# Focuser.net
KiCad netlist of a schematic drawn in EAGLE
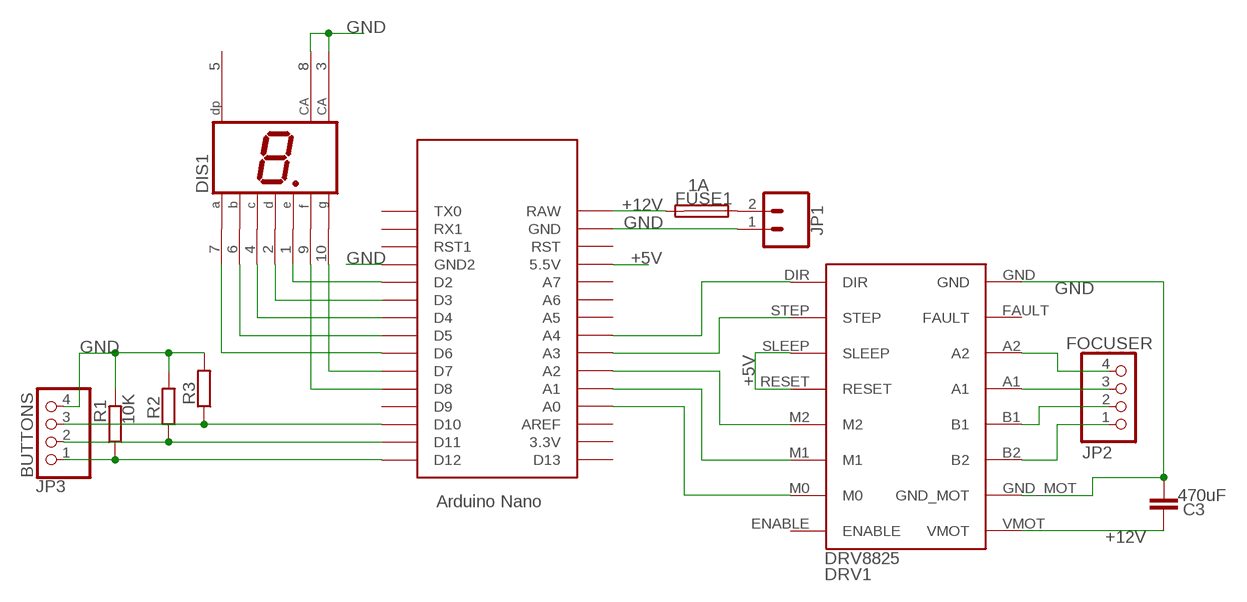
[diagram p0: schematic, sheet 1]

(export (version "E")
  (design (tool "Eeschema 10.0.6"))
  (components
    (comp (ref "C3")
      (value "470uF")
      (footprint "eagle-import:C5B2.5")
      (fields (field (name "SPICEPREFIX") "C"))
      (libsource (lib "eagle-import") (part "C5/2.5"))
    )
    (comp (ref "DIS1")
      (value "HD-H101")
      (footprint "eagle-import:HDSP-M")
      (fields (field (name "SPICEPREFIX") "X"))
      (libsource (lib "eagle-import") (part "HD-H101"))
    )
    (comp (ref "DRV1")
      (value "DRV8825")
      (footprint "eagle-import:DRV8825")
      (fields (field (name "SPICEPREFIX") "X"))
      (libsource (lib "eagle-import") (part "DRV8825"))
    )
    (comp (ref "FUSE1")
      (value "1A")
      (footprint "eagle-import:FUSE_HOLDER_5X20MM")
      (fields (field (name "SPICEPREFIX") "F"))
      (libsource (lib "eagle-import") (part "FUSEBLANK_5X20MM"))
    )
    (comp (ref "JP1")
      (value "CONN_025MM")
      (footprint "eagle-import:SCREWTERMINAL-5MM-2")
      (fields (field (name "SPICEPREFIX") "B"))
      (libsource (lib "eagle-import") (part "CONN_025MM"))
    )
    (comp (ref "JP2")
      (value "FOCUSER")
      (footprint "eagle-import:1X04")
      (fields (field (name "SPICEPREFIX") "E"))
      (libsource (lib "eagle-import") (part "PINHD-1X4"))
    )
    (comp (ref "JP3")
      (value "BUTTONS")
      (footprint "eagle-import:1X04")
      (fields (field (name "SPICEPREFIX") "E"))
      (libsource (lib "eagle-import") (part "PINHD-1X4"))
    )
    (comp (ref "R1")
      (value "10K")
      (footprint "eagle-import:0204V")
      (fields (field (name "SPICEPREFIX") "R"))
      (libsource (lib "eagle-import") (part "R-EU_0204/2V"))
    )
    (comp (ref "R2")
      (value "10K")
      (footprint "eagle-import:0204V")
      (fields (field (name "SPICEPREFIX") "R"))
      (libsource (lib "eagle-import") (part "R-EU_0204/2V"))
    )
    (comp (ref "R3")
      (value "10K")
      (footprint "eagle-import:0204V")
      (fields (field (name "SPICEPREFIX") "R"))
      (libsource (lib "eagle-import") (part "R-EU_0204/2V"))
    )
    (comp (ref "U$1")
      (value "NANO")
      (footprint "eagle-import:NANO")
      (fields (field (name "SPICEPREFIX") "X"))
      (libsource (lib "eagle-import") (part "NANO"))
    )
  )
  (nets
    (net (code "1") (name "/+5V") (class "Default")
      (node (ref "DRV1") (pin "RESET") (pinfunction "RESET_RESET") (pintype "bidirectional"))
      (node (ref "DRV1") (pin "SLEEP") (pinfunction "SLEEP_SLEEP") (pintype "bidirectional"))
      (node (ref "U$1") (pin "5V") (pinfunction "5.5V_5V") (pintype "bidirectional"))
    )
    (net (code "2") (name "/+12V") (class "Default")
      (node (ref "C3") (pin "2") (pinfunction "2_2") (pintype "passive"))
      (node (ref "DRV1") (pin "VMOT") (pinfunction "VMOT_VMOT") (pintype "bidirectional"))
      (node (ref "FUSE1") (pin "2") (pinfunction "2_2") (pintype "passive"))
      (node (ref "U$1") (pin "RAW") (pinfunction "RAW_RAW") (pintype "bidirectional"))
    )
    (net (code "3") (name "/GND") (class "Default")
      (node (ref "C3") (pin "1") (pinfunction "1_1") (pintype "passive"))
      (node (ref "DIS1") (pin "3") (pinfunction "CA_3") (pintype "passive"))
      (node (ref "DIS1") (pin "8") (pinfunction "CA_8") (pintype "passive"))
      (node (ref "DRV1") (pin "GND") (pinfunction "GND_GND") (pintype "bidirectional"))
      (node (ref "DRV1") (pin "GND_MOT") (pinfunction "GND_MOT_GND_MOT") (pintype "bidirectional"))
      (node (ref "JP1") (pin "1") (pinfunction "1_1") (pintype "passive"))
      (node (ref "JP3") (pin "4") (pinfunction "4_4") (pintype "passive"))
      (node (ref "R1") (pin "2") (pinfunction "2_2") (pintype "passive"))
      (node (ref "R2") (pin "2") (pinfunction "2_2") (pintype "passive"))
      (node (ref "R3") (pin "2") (pinfunction "2_2") (pintype "passive"))
      (node (ref "U$1") (pin "GND") (pinfunction "GND_GND") (pintype "bidirectional"))
      (node (ref "U$1") (pin "GND1") (pinfunction "GND2_GND1") (pintype "bidirectional"))
    )
    (net (code "4") (name "Net-(DIS1-A)") (class "Default")
      (node (ref "DIS1") (pin "7") (pinfunction "A_7") (pintype "passive"))
      (node (ref "U$1") (pin "D6") (pinfunction "D6_D6") (pintype "bidirectional"))
    )
    (net (code "5") (name "Net-(DIS1-B)") (class "Default")
      (node (ref "DIS1") (pin "6") (pinfunction "B_6") (pintype "passive"))
      (node (ref "U$1") (pin "D5") (pinfunction "D5_D5") (pintype "bidirectional"))
    )
    (net (code "6") (name "Net-(DIS1-C)") (class "Default")
      (node (ref "DIS1") (pin "4") (pinfunction "C_4") (pintype "passive"))
      (node (ref "U$1") (pin "D4") (pinfunction "D4_D4") (pintype "bidirectional"))
    )
    (net (code "7") (name "Net-(DIS1-D)") (class "Default")
      (node (ref "DIS1") (pin "2") (pinfunction "D_2") (pintype "passive"))
      (node (ref "U$1") (pin "D3") (pinfunction "D3_D3") (pintype "bidirectional"))
    )
    (net (code "8") (name "Net-(DIS1-E)") (class "Default")
      (node (ref "DIS1") (pin "1") (pinfunction "E_1") (pintype "passive"))
      (node (ref "U$1") (pin "D2") (pinfunction "D2_D2") (pintype "bidirectional"))
    )
    (net (code "9") (name "Net-(DIS1-F)") (class "Default")
      (node (ref "DIS1") (pin "9") (pinfunction "F_9") (pintype "passive"))
      (node (ref "U$1") (pin "D8") (pinfunction "D8_D8") (pintype "bidirectional"))
    )
    (net (code "10") (name "Net-(DIS1-G)") (class "Default")
      (node (ref "DIS1") (pin "10") (pinfunction "G_10") (pintype "passive"))
      (node (ref "U$1") (pin "D7") (pinfunction "D7_D7") (pintype "bidirectional"))
    )
    (net (code "11") (name "Net-(DRV1-PadA1)") (class "Default")
      (node (ref "DRV1") (pin "A1") (pinfunction "A1_A1") (pintype "bidirectional"))
      (node (ref "JP2") (pin "3") (pinfunction "3_3") (pintype "passive"))
    )
    (net (code "12") (name "Net-(DRV1-PadA2)") (class "Default")
      (node (ref "DRV1") (pin "A2") (pinfunction "A2_A2") (pintype "bidirectional"))
      (node (ref "JP2") (pin "4") (pinfunction "4_4") (pintype "passive"))
    )
    (net (code "13") (name "Net-(DRV1-PadB1)") (class "Default")
      (node (ref "DRV1") (pin "B1") (pinfunction "B1_B1") (pintype "bidirectional"))
      (node (ref "JP2") (pin "2") (pinfunction "2_2") (pintype "passive"))
    )
    (net (code "14") (name "Net-(DRV1-PadB2)") (class "Default")
      (node (ref "DRV1") (pin "B2") (pinfunction "B2_B2") (pintype "bidirectional"))
      (node (ref "JP2") (pin "1") (pinfunction "1_1") (pintype "passive"))
    )
    (net (code "15") (name "Net-(DRV1-PadDIR)") (class "Default")
      (node (ref "DRV1") (pin "DIR") (pinfunction "DIR_DIR") (pintype "bidirectional"))
      (node (ref "U$1") (pin "A4") (pinfunction "A4_A4") (pintype "bidirectional"))
    )
    (net (code "16") (name "Net-(DRV1-PadM0)") (class "Default")
      (node (ref "DRV1") (pin "M0") (pinfunction "M0_M0") (pintype "bidirectional"))
      (node (ref "U$1") (pin "A0") (pinfunction "A0_A0") (pintype "bidirectional"))
    )
    (net (code "17") (name "Net-(DRV1-PadM1)") (class "Default")
      (node (ref "DRV1") (pin "M1") (pinfunction "M1_M1") (pintype "bidirectional"))
      (node (ref "U$1") (pin "A1") (pinfunction "A1_A1") (pintype "bidirectional"))
    )
    (net (code "18") (name "Net-(DRV1-PadM2)") (class "Default")
      (node (ref "DRV1") (pin "M2") (pinfunction "M2_M2") (pintype "bidirectional"))
      (node (ref "U$1") (pin "A2") (pinfunction "A2_A2") (pintype "bidirectional"))
    )
    (net (code "19") (name "Net-(DRV1-PadSTEP)") (class "Default")
      (node (ref "DRV1") (pin "STEP") (pinfunction "STEP_STEP") (pintype "bidirectional"))
      (node (ref "U$1") (pin "A3") (pinfunction "A3_A3") (pintype "bidirectional"))
    )
    (net (code "20") (name "Net-(FUSE1-Pad1)") (class "Default")
      (node (ref "FUSE1") (pin "1") (pinfunction "1_1") (pintype "passive"))
      (node (ref "JP1") (pin "2") (pinfunction "2_2") (pintype "passive"))
    )
    (net (code "21") (name "Net-(JP3-Pad1)") (class "Default")
      (node (ref "JP3") (pin "1") (pinfunction "1_1") (pintype "passive"))
      (node (ref "R1") (pin "1") (pinfunction "1_1") (pintype "passive"))
      (node (ref "U$1") (pin "D12") (pinfunction "D12_D12") (pintype "bidirectional"))
    )
    (net (code "22") (name "Net-(JP3-Pad2)") (class "Default")
      (node (ref "JP3") (pin "2") (pinfunction "2_2") (pintype "passive"))
      (node (ref "R2") (pin "1") (pinfunction "1_1") (pintype "passive"))
      (node (ref "U$1") (pin "D11") (pinfunction "D11_D11") (pintype "bidirectional"))
    )
    (net (code "23") (name "Net-(JP3-Pad3)") (class "Default")
      (node (ref "JP3") (pin "3") (pinfunction "3_3") (pintype "passive"))
      (node (ref "R3") (pin "1") (pinfunction "1_1") (pintype "passive"))
      (node (ref "U$1") (pin "D10") (pinfunction "D10_D10") (pintype "bidirectional"))
    )
    (net (code "24") (name "unconnected-(DIS1-DP-Pad5)") (class "Default")
      (node (ref "DIS1") (pin "5") (pinfunction "DP_5") (pintype "passive"))
    )
    (net (code "25") (name "unconnected-(DRV1-PadENABLE)") (class "Default")
      (node (ref "DRV1") (pin "ENABLE") (pinfunction "ENABLE_ENABLE") (pintype "bidirectional"))
    )
    (net (code "26") (name "unconnected-(DRV1-PadFAULT)") (class "Default")
      (node (ref "DRV1") (pin "FAULT") (pinfunction "FAULT_FAULT") (pintype "bidirectional"))
    )
    (net (code "27") (name "unconnected-(U$1-Pad3.3V)") (class "Default")
      (node (ref "U$1") (pin "3.3V") (pinfunction "3.3V_3.3V") (pintype "bidirectional"))
    )
    (net (code "28") (name "unconnected-(U$1-PadA5)") (class "Default")
      (node (ref "U$1") (pin "A5") (pinfunction "A5_A5") (pintype "bidirectional"))
    )
    (net (code "29") (name "unconnected-(U$1-PadA6)") (class "Default")
      (node (ref "U$1") (pin "A6") (pinfunction "A6_A6") (pintype "bidirectional"))
    )
    (net (code "30") (name "unconnected-(U$1-PadA7)") (class "Default")
      (node (ref "U$1") (pin "A7") (pinfunction "A7_A7") (pintype "bidirectional"))
    )
    (net (code "31") (name "unconnected-(U$1-PadAREF)") (class "Default")
      (node (ref "U$1") (pin "AREF") (pinfunction "AREF_AREF") (pintype "bidirectional"))
    )
    (net (code "32") (name "unconnected-(U$1-PadD9)") (class "Default")
      (node (ref "U$1") (pin "D9") (pinfunction "D9_D9") (pintype "bidirectional"))
    )
    (net (code "33") (name "unconnected-(U$1-PadD13)") (class "Default")
      (node (ref "U$1") (pin "D13") (pinfunction "D13_D13") (pintype "bidirectional"))
    )
    (net (code "34") (name "unconnected-(U$1-PadICSP1)") (class "Default")
      (node (ref "U$1") (pin "ICSP1") (pinfunction "ICSP1_ICSP1") (pintype "bidirectional"))
    )
    (net (code "35") (name "unconnected-(U$1-PadICSP2)") (class "Default")
      (node (ref "U$1") (pin "ICSP2") (pinfunction "ICSP2_ICSP2") (pintype "bidirectional"))
    )
    (net (code "36") (name "unconnected-(U$1-PadICSP3)") (class "Default")
      (node (ref "U$1") (pin "ICSP3") (pinfunction "ICSP3_ICSP3") (pintype "bidirectional"))
    )
    (net (code "37") (name "unconnected-(U$1-PadICSP4)") (class "Default")
      (node (ref "U$1") (pin "ICSP4") (pinfunction "ICSP4_ICSP4") (pintype "bidirectional"))
    )
    (net (code "38") (name "unconnected-(U$1-PadICSP5)") (class "Default")
      (node (ref "U$1") (pin "ICSP5") (pinfunction "ICSP5_ICSP5") (pintype "bidirectional"))
    )
    (net (code "39") (name "unconnected-(U$1-PadICSP6)") (class "Default")
      (node (ref "U$1") (pin "ICSP6") (pinfunction "ICSP6_ICSP6") (pintype "bidirectional"))
    )
    (net (code "40") (name "unconnected-(U$1-PadRST)") (class "Default")
      (node (ref "U$1") (pin "RST") (pinfunction "RST_RST") (pintype "bidirectional"))
    )
    (net (code "41") (name "unconnected-(U$1-PadRST1)") (class "Default")
      (node (ref "U$1") (pin "RST1") (pinfunction "RST1_RST1") (pintype "bidirectional"))
    )
    (net (code "42") (name "unconnected-(U$1-PadRX1)") (class "Default")
      (node (ref "U$1") (pin "RX1") (pinfunction "RX1_RX1") (pintype "bidirectional"))
    )
    (net (code "43") (name "unconnected-(U$1-PadTX0)") (class "Default")
      (node (ref "U$1") (pin "TX0") (pinfunction "TX0_TX0") (pintype "bidirectional"))
    )
  )
)
